# SensorBoard.net
KiCad netlist of a schematic drawn in EAGLE
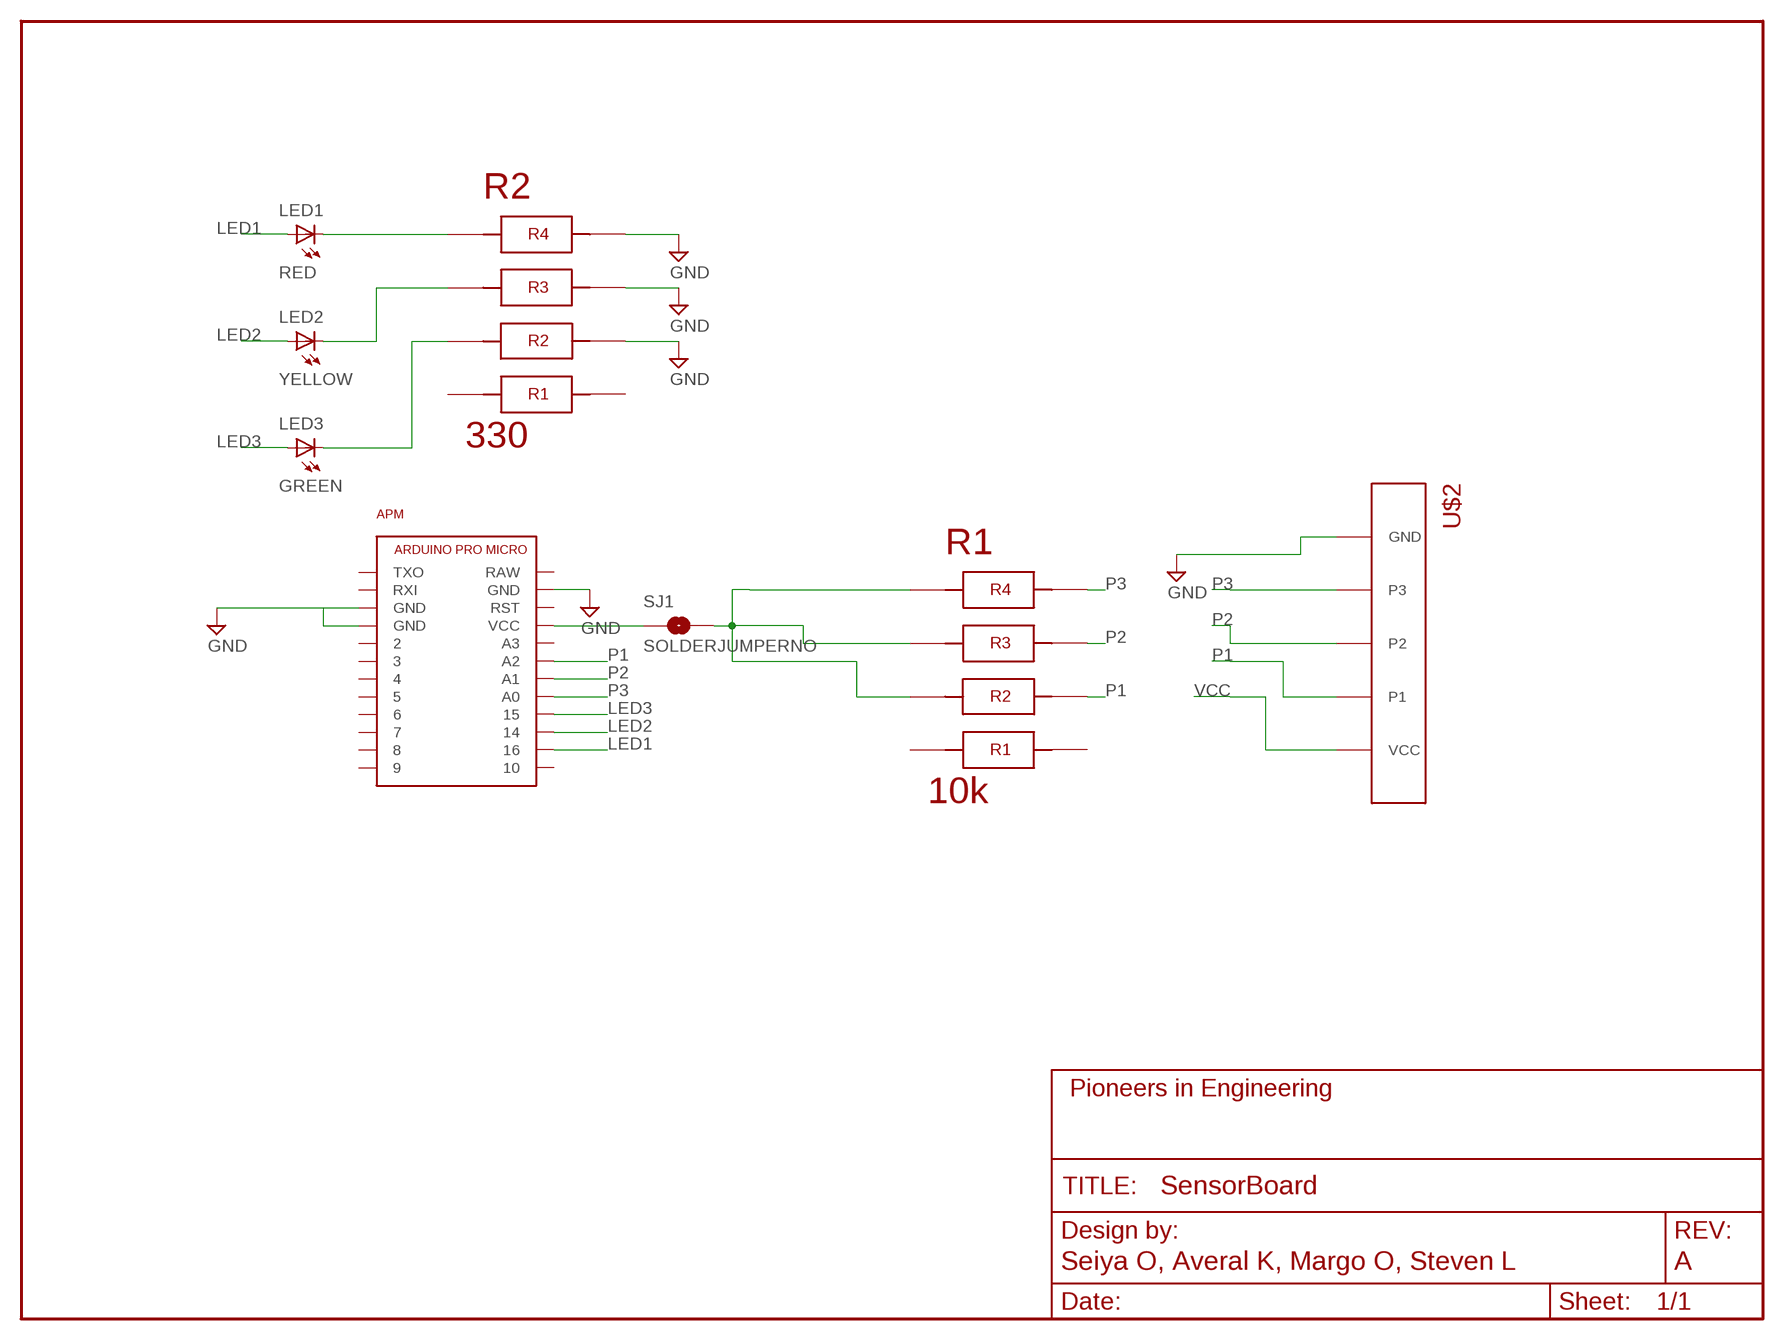
[diagram p0: schematic, sheet 1]

(export (version "E")
  (design (tool "Eeschema 10.0.6"))
  (components
    (comp (ref "APM")
      (value "ARDUINO_PRO_MICRO")
      (footprint "eagle-import:ARDUINO_PRO_MICRO")
      (fields
        (field (name "DISTRIBUTOR_PART_NUMBER") "32284746884")
        (field (name "MANUFACTURER") "Feiyang electronics")
      )
      (libsource (lib "eagle-import") (part "ARDUINO_PRO_MICRO"))
    )
    (comp (ref "LED1")
      (value "RED")
      (footprint "eagle-import:LED-1206")
      (libsource (lib "eagle-import") (part "LED1206"))
    )
    (comp (ref "LED2")
      (value "YELLOW")
      (footprint "eagle-import:LED-1206")
      (libsource (lib "eagle-import") (part "LED1206"))
    )
    (comp (ref "LED3")
      (value "GREEN")
      (footprint "eagle-import:LED-1206")
      (libsource (lib "eagle-import") (part "LED1206"))
    )
    (comp (ref "R1")
      (value "10k")
      (footprint "eagle-import:4X-0603")
      (libsource (lib "eagle-import") (part "4X-0603"))
    )
    (comp (ref "R2")
      (value "330")
      (footprint "eagle-import:4X-0603")
      (libsource (lib "eagle-import") (part "4X-0603"))
    )
    (comp (ref "SJ1")
      (value "SOLDERJUMPERNO")
      (footprint "eagle-import:SJ_2S-NO")
      (libsource (lib "eagle-import") (part "SOLDERJUMPERNO"))
    )
    (comp (ref "U$2")
      (value "5PIN")
      (footprint "eagle-import:5PIN")
      (libsource (lib "eagle-import") (part "5PIN"))
    )
  )
  (nets
    (net (code "1") (name "/LED1") (class "Default")
      (node (ref "APM") (pin "16") (pinfunction "16_16") (pintype "bidirectional"))
      (node (ref "LED1") (pin "A") (pinfunction "A_A") (pintype "passive"))
    )
    (net (code "2") (name "/LED2") (class "Default")
      (node (ref "APM") (pin "14") (pinfunction "14_14") (pintype "bidirectional"))
      (node (ref "LED2") (pin "A") (pinfunction "A_A") (pintype "passive"))
    )
    (net (code "3") (name "/LED3") (class "Default")
      (node (ref "APM") (pin "15") (pinfunction "15_15") (pintype "bidirectional"))
      (node (ref "LED3") (pin "A") (pinfunction "A_A") (pintype "passive"))
    )
    (net (code "4") (name "/P1") (class "Default")
      (node (ref "APM") (pin "A2") (pinfunction "A2_A2") (pintype "bidirectional"))
      (node (ref "R1") (pin "2") (pinfunction "2_2") (pintype "bidirectional"))
      (node (ref "U$2") (pin "P1") (pinfunction "P1_P1") (pintype "bidirectional"))
    )
    (net (code "5") (name "/P2") (class "Default")
      (node (ref "APM") (pin "A1") (pinfunction "A1_A1") (pintype "bidirectional"))
      (node (ref "R1") (pin "3") (pinfunction "3_3") (pintype "bidirectional"))
      (node (ref "U$2") (pin "P2") (pinfunction "P2_P2") (pintype "bidirectional"))
    )
    (net (code "6") (name "/P3") (class "Default")
      (node (ref "APM") (pin "A0") (pinfunction "A0_A0") (pintype "bidirectional"))
      (node (ref "R1") (pin "4") (pinfunction "4_4") (pintype "bidirectional"))
      (node (ref "U$2") (pin "P3") (pinfunction "P3_P3") (pintype "bidirectional"))
    )
    (net (code "7") (name "/VCC") (class "Default")
      (node (ref "APM") (pin "VCC") (pinfunction "VCC_VCC") (pintype "bidirectional"))
      (node (ref "SJ1") (pin "1") (pinfunction "1_1") (pintype "passive"))
      (node (ref "U$2") (pin "VCC") (pinfunction "VCC_VCC") (pintype "bidirectional"))
    )
    (net (code "8") (name "GND") (class "Default")
      (node (ref "APM") (pin "GND@0") (pinfunction "GND_GND@0") (pintype "bidirectional"))
      (node (ref "APM") (pin "GND@1") (pinfunction "GND_GND@1") (pintype "bidirectional"))
      (node (ref "APM") (pin "GND@2") (pinfunction "GND_GND@2") (pintype "bidirectional"))
      (node (ref "R2") (pin "2") (pinfunction "2_2") (pintype "bidirectional"))
      (node (ref "R2") (pin "3") (pinfunction "3_3") (pintype "bidirectional"))
      (node (ref "R2") (pin "4") (pinfunction "4_4") (pintype "bidirectional"))
      (node (ref "U$2") (pin "GND") (pinfunction "GND_GND") (pintype "bidirectional"))
    )
    (net (code "9") (name "Net-(LED1-PadC)") (class "Default")
      (node (ref "LED1") (pin "C") (pinfunction "C_C") (pintype "passive"))
      (node (ref "R2") (pin "5") (pinfunction "5_5") (pintype "bidirectional"))
    )
    (net (code "10") (name "Net-(LED2-PadC)") (class "Default")
      (node (ref "LED2") (pin "C") (pinfunction "C_C") (pintype "passive"))
      (node (ref "R2") (pin "6") (pinfunction "6_6") (pintype "bidirectional"))
    )
    (net (code "11") (name "Net-(LED3-PadC)") (class "Default")
      (node (ref "LED3") (pin "C") (pinfunction "C_C") (pintype "passive"))
      (node (ref "R2") (pin "7") (pinfunction "7_7") (pintype "bidirectional"))
    )
    (net (code "12") (name "Net-(R1-Pad5)") (class "Default")
      (node (ref "R1") (pin "5") (pinfunction "5_5") (pintype "bidirectional"))
      (node (ref "R1") (pin "6") (pinfunction "6_6") (pintype "bidirectional"))
      (node (ref "R1") (pin "7") (pinfunction "7_7") (pintype "bidirectional"))
      (node (ref "SJ1") (pin "2") (pinfunction "2_2") (pintype "passive"))
    )
    (net (code "13") (name "unconnected-(APM-Pad2)") (class "Default")
      (node (ref "APM") (pin "2") (pinfunction "2_2") (pintype "bidirectional"))
    )
    (net (code "14") (name "unconnected-(APM-Pad3)") (class "Default")
      (node (ref "APM") (pin "3") (pinfunction "3_3") (pintype "bidirectional"))
    )
    (net (code "15") (name "unconnected-(APM-Pad4)") (class "Default")
      (node (ref "APM") (pin "4") (pinfunction "4_4") (pintype "bidirectional"))
    )
    (net (code "16") (name "unconnected-(APM-Pad5)") (class "Default")
      (node (ref "APM") (pin "5") (pinfunction "5_5") (pintype "bidirectional"))
    )
    (net (code "17") (name "unconnected-(APM-Pad6)") (class "Default")
      (node (ref "APM") (pin "6") (pinfunction "6_6") (pintype "bidirectional"))
    )
    (net (code "18") (name "unconnected-(APM-Pad7)") (class "Default")
      (node (ref "APM") (pin "7") (pinfunction "7_7") (pintype "bidirectional"))
    )
    (net (code "19") (name "unconnected-(APM-Pad8)") (class "Default")
      (node (ref "APM") (pin "8") (pinfunction "8_8") (pintype "bidirectional"))
    )
    (net (code "20") (name "unconnected-(APM-Pad9)") (class "Default")
      (node (ref "APM") (pin "9") (pinfunction "9_9") (pintype "bidirectional"))
    )
    (net (code "21") (name "unconnected-(APM-Pad10)") (class "Default")
      (node (ref "APM") (pin "10") (pinfunction "10_10") (pintype "bidirectional"))
    )
    (net (code "22") (name "unconnected-(APM-PadA3)") (class "Default")
      (node (ref "APM") (pin "A3") (pinfunction "A3_A3") (pintype "bidirectional"))
    )
    (net (code "23") (name "unconnected-(APM-PadRAW)") (class "Default")
      (node (ref "APM") (pin "RAW") (pinfunction "RAW_RAW") (pintype "bidirectional"))
    )
    (net (code "24") (name "unconnected-(APM-PadRST)") (class "Default")
      (node (ref "APM") (pin "RST") (pinfunction "RST_RST") (pintype "bidirectional"))
    )
    (net (code "25") (name "unconnected-(APM-PadRXI)") (class "Default")
      (node (ref "APM") (pin "RXI") (pinfunction "RXI_RXI") (pintype "bidirectional"))
    )
    (net (code "26") (name "unconnected-(APM-PadTXO)") (class "Default")
      (node (ref "APM") (pin "TXO") (pinfunction "TXO_TXO") (pintype "bidirectional"))
    )
    (net (code "27") (name "unconnected-(R1-Pad1)") (class "Default")
      (node (ref "R1") (pin "1") (pinfunction "1_1") (pintype "bidirectional"))
    )
    (net (code "28") (name "unconnected-(R1-Pad8)") (class "Default")
      (node (ref "R1") (pin "8") (pinfunction "8_8") (pintype "bidirectional"))
    )
    (net (code "29") (name "unconnected-(R2-Pad1)") (class "Default")
      (node (ref "R2") (pin "1") (pinfunction "1_1") (pintype "bidirectional"))
    )
    (net (code "30") (name "unconnected-(R2-Pad8)") (class "Default")
      (node (ref "R2") (pin "8") (pinfunction "8_8") (pintype "bidirectional"))
    )
  )
)
